# Laser_Array_Temp.net
KiCad netlist of a schematic drawn in EAGLE
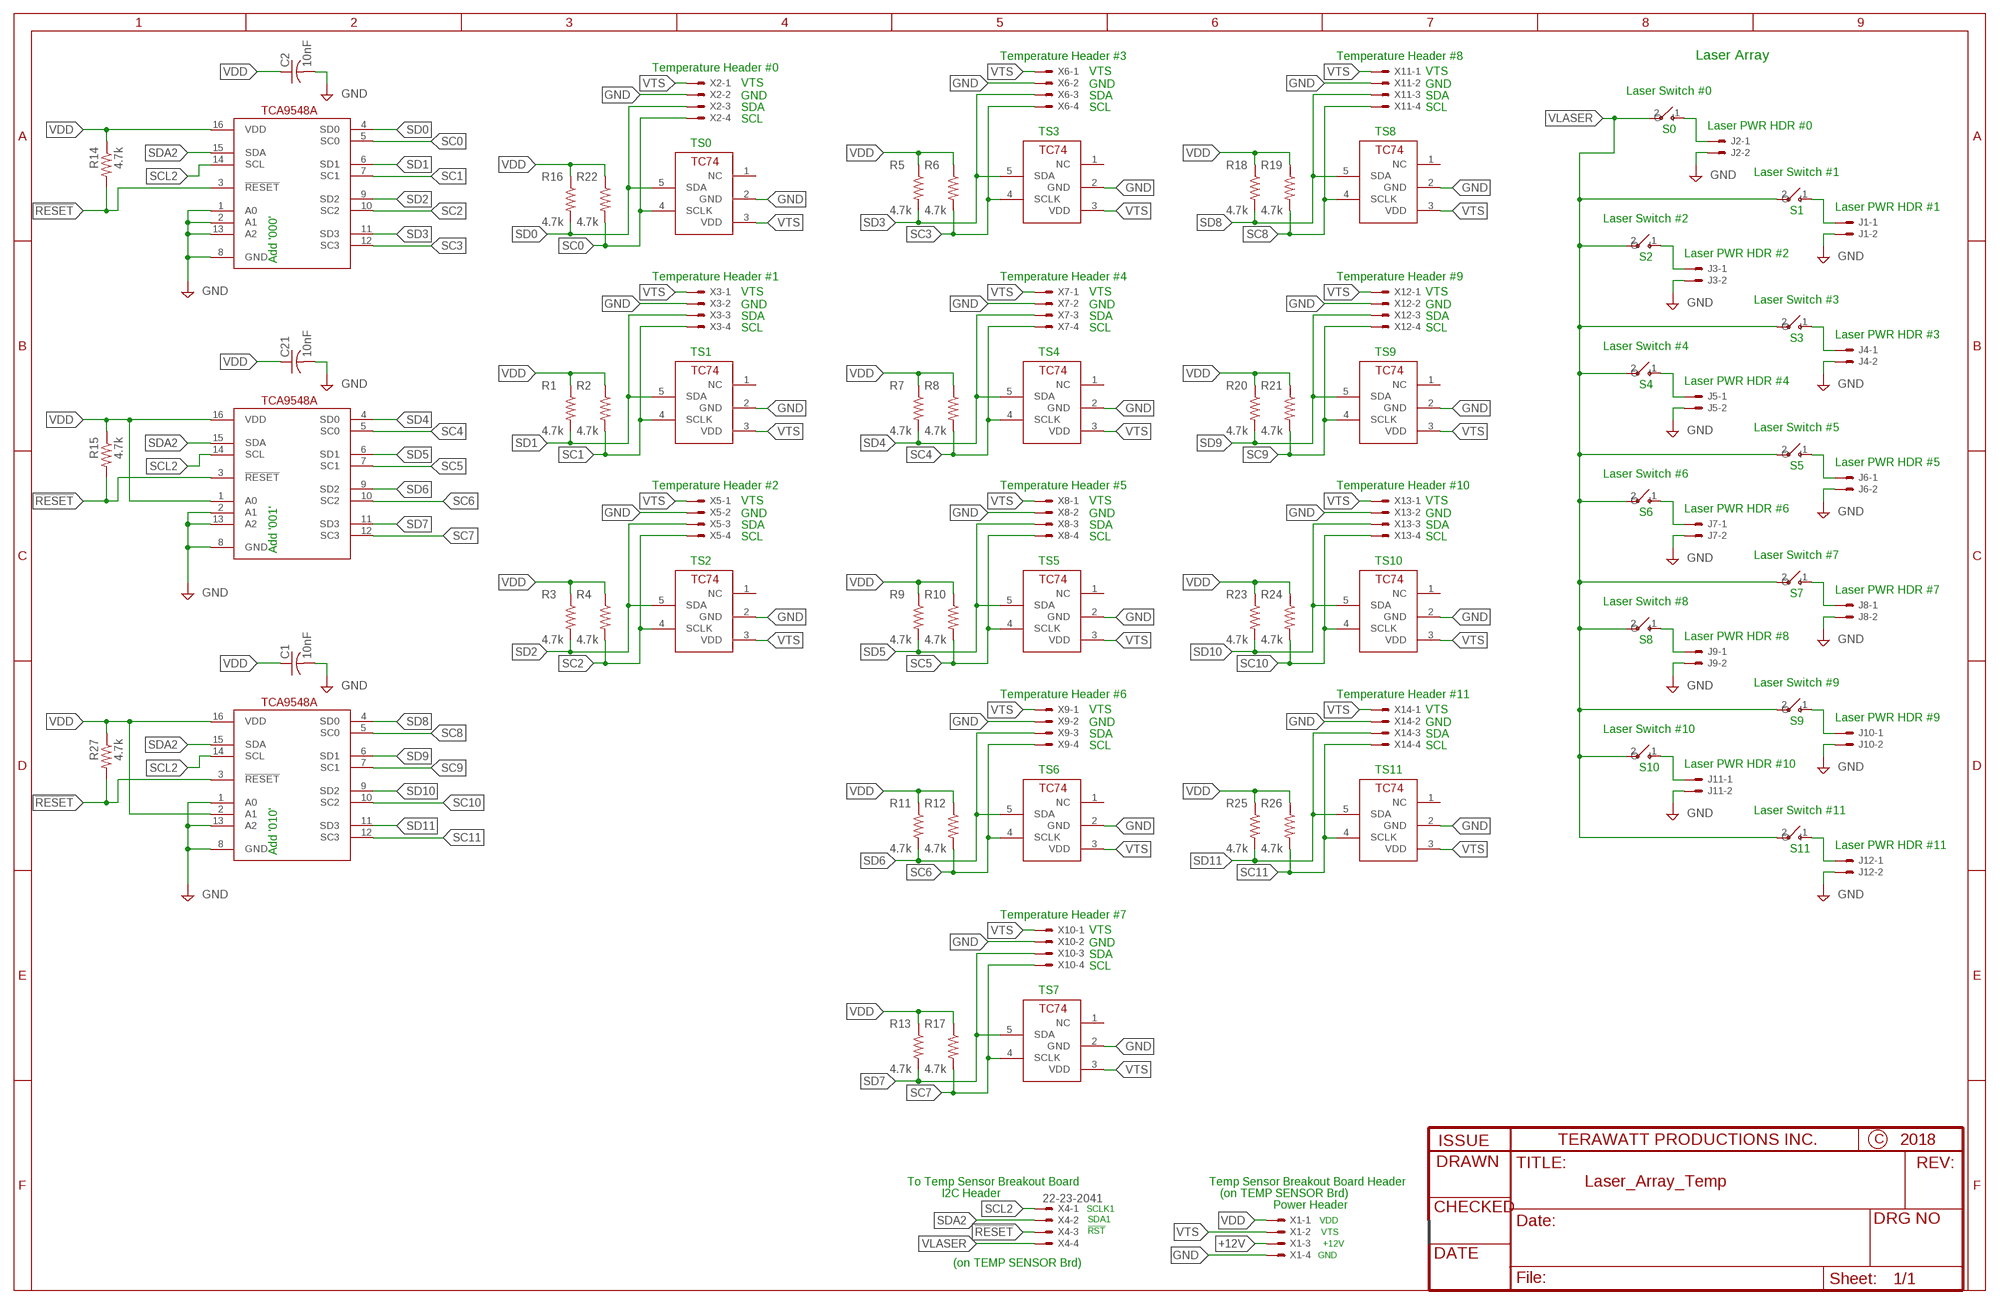
[diagram p0: schematic, sheet 1]

(export (version "E")
  (design (tool "Eeschema 10.0.6"))
  (components
    (comp (ref "C1")
      (value "10nF")
      (footprint "eagle-import:C0805")
      (libsource (lib "eagle-import") (part "C-USC0805"))
    )
    (comp (ref "C2")
      (value "10nF")
      (footprint "eagle-import:C0805")
      (libsource (lib "eagle-import") (part "C-USC0805"))
    )
    (comp (ref "C21")
      (value "10nF")
      (footprint "eagle-import:C0805")
      (libsource (lib "eagle-import") (part "C-USC0805"))
    )
    (comp (ref "J1")
      (value "22-23-2021")
      (footprint "eagle-import:22-23-2021")
      (fields (field (name "MF") "MOLEX"))
      (libsource (lib "eagle-import") (part "22-23-2021"))
    )
    (comp (ref "J2")
      (value "22-23-2021")
      (footprint "eagle-import:22-23-2021")
      (fields (field (name "MF") "MOLEX"))
      (libsource (lib "eagle-import") (part "22-23-2021"))
    )
    (comp (ref "J3")
      (value "22-23-2021")
      (footprint "eagle-import:22-23-2021")
      (fields (field (name "MF") "MOLEX"))
      (libsource (lib "eagle-import") (part "22-23-2021"))
    )
    (comp (ref "J4")
      (value "22-23-2021")
      (footprint "eagle-import:22-23-2021")
      (fields (field (name "MF") "MOLEX"))
      (libsource (lib "eagle-import") (part "22-23-2021"))
    )
    (comp (ref "J5")
      (value "22-23-2021")
      (footprint "eagle-import:22-23-2021")
      (fields (field (name "MF") "MOLEX"))
      (libsource (lib "eagle-import") (part "22-23-2021"))
    )
    (comp (ref "J6")
      (value "22-23-2021")
      (footprint "eagle-import:22-23-2021")
      (fields (field (name "MF") "MOLEX"))
      (libsource (lib "eagle-import") (part "22-23-2021"))
    )
    (comp (ref "J7")
      (value "22-23-2021")
      (footprint "eagle-import:22-23-2021")
      (fields (field (name "MF") "MOLEX"))
      (libsource (lib "eagle-import") (part "22-23-2021"))
    )
    (comp (ref "J8")
      (value "22-23-2021")
      (footprint "eagle-import:22-23-2021")
      (fields (field (name "MF") "MOLEX"))
      (libsource (lib "eagle-import") (part "22-23-2021"))
    )
    (comp (ref "J9")
      (value "22-23-2021")
      (footprint "eagle-import:22-23-2021")
      (fields (field (name "MF") "MOLEX"))
      (libsource (lib "eagle-import") (part "22-23-2021"))
    )
    (comp (ref "J10")
      (value "22-23-2021")
      (footprint "eagle-import:22-23-2021")
      (fields (field (name "MF") "MOLEX"))
      (libsource (lib "eagle-import") (part "22-23-2021"))
    )
    (comp (ref "J11")
      (value "22-23-2021")
      (footprint "eagle-import:22-23-2021")
      (fields (field (name "MF") "MOLEX"))
      (libsource (lib "eagle-import") (part "22-23-2021"))
    )
    (comp (ref "J12")
      (value "22-23-2021")
      (footprint "eagle-import:22-23-2021")
      (fields (field (name "MF") "MOLEX"))
      (libsource (lib "eagle-import") (part "22-23-2021"))
    )
    (comp (ref "R1")
      (value "4.7k")
      (footprint "eagle-import:M0805")
      (libsource (lib "eagle-import") (part "R-US_M0805"))
    )
    (comp (ref "R2")
      (value "4.7k")
      (footprint "eagle-import:M0805")
      (libsource (lib "eagle-import") (part "R-US_M0805"))
    )
    (comp (ref "R3")
      (value "4.7k")
      (footprint "eagle-import:M0805")
      (libsource (lib "eagle-import") (part "R-US_M0805"))
    )
    (comp (ref "R4")
      (value "4.7k")
      (footprint "eagle-import:M0805")
      (libsource (lib "eagle-import") (part "R-US_M0805"))
    )
    (comp (ref "R5")
      (value "4.7k")
      (footprint "eagle-import:M0805")
      (libsource (lib "eagle-import") (part "R-US_M0805"))
    )
    (comp (ref "R6")
      (value "4.7k")
      (footprint "eagle-import:M0805")
      (libsource (lib "eagle-import") (part "R-US_M0805"))
    )
    (comp (ref "R7")
      (value "4.7k")
      (footprint "eagle-import:M0805")
      (libsource (lib "eagle-import") (part "R-US_M0805"))
    )
    (comp (ref "R8")
      (value "4.7k")
      (footprint "eagle-import:M0805")
      (libsource (lib "eagle-import") (part "R-US_M0805"))
    )
    (comp (ref "R9")
      (value "4.7k")
      (footprint "eagle-import:M0805")
      (libsource (lib "eagle-import") (part "R-US_M0805"))
    )
    (comp (ref "R10")
      (value "4.7k")
      (footprint "eagle-import:M0805")
      (libsource (lib "eagle-import") (part "R-US_M0805"))
    )
    (comp (ref "R11")
      (value "4.7k")
      (footprint "eagle-import:M0805")
      (libsource (lib "eagle-import") (part "R-US_M0805"))
    )
    (comp (ref "R12")
      (value "4.7k")
      (footprint "eagle-import:M0805")
      (libsource (lib "eagle-import") (part "R-US_M0805"))
    )
    (comp (ref "R13")
      (value "4.7k")
      (footprint "eagle-import:M0805")
      (libsource (lib "eagle-import") (part "R-US_M0805"))
    )
    (comp (ref "R14")
      (value "4.7k")
      (footprint "eagle-import:M0805")
      (libsource (lib "eagle-import") (part "R-US_M0805"))
    )
    (comp (ref "R15")
      (value "4.7k")
      (footprint "eagle-import:M0805")
      (libsource (lib "eagle-import") (part "R-US_M0805"))
    )
    (comp (ref "R16")
      (value "4.7k")
      (footprint "eagle-import:M0805")
      (libsource (lib "eagle-import") (part "R-US_M0805"))
    )
    (comp (ref "R17")
      (value "4.7k")
      (footprint "eagle-import:M0805")
      (libsource (lib "eagle-import") (part "R-US_M0805"))
    )
    (comp (ref "R18")
      (value "4.7k")
      (footprint "eagle-import:M0805")
      (libsource (lib "eagle-import") (part "R-US_M0805"))
    )
    (comp (ref "R19")
      (value "4.7k")
      (footprint "eagle-import:M0805")
      (libsource (lib "eagle-import") (part "R-US_M0805"))
    )
    (comp (ref "R20")
      (value "4.7k")
      (footprint "eagle-import:M0805")
      (libsource (lib "eagle-import") (part "R-US_M0805"))
    )
    (comp (ref "R21")
      (value "4.7k")
      (footprint "eagle-import:M0805")
      (libsource (lib "eagle-import") (part "R-US_M0805"))
    )
    (comp (ref "R22")
      (value "4.7k")
      (footprint "eagle-import:M0805")
      (libsource (lib "eagle-import") (part "R-US_M0805"))
    )
    (comp (ref "R23")
      (value "4.7k")
      (footprint "eagle-import:M0805")
      (libsource (lib "eagle-import") (part "R-US_M0805"))
    )
    (comp (ref "R24")
      (value "4.7k")
      (footprint "eagle-import:M0805")
      (libsource (lib "eagle-import") (part "R-US_M0805"))
    )
    (comp (ref "R25")
      (value "4.7k")
      (footprint "eagle-import:M0805")
      (libsource (lib "eagle-import") (part "R-US_M0805"))
    )
    (comp (ref "R26")
      (value "4.7k")
      (footprint "eagle-import:M0805")
      (libsource (lib "eagle-import") (part "R-US_M0805"))
    )
    (comp (ref "R27")
      (value "4.7k")
      (footprint "eagle-import:M0805")
      (libsource (lib "eagle-import") (part "R-US_M0805"))
    )
    (comp (ref "S13")
      (value "TOGGLE_SPST")
      (footprint "eagle-import:22-23-2021")
      (libsource (lib "eagle-import") (part "TOGGLE_SPST"))
    )
    (comp (ref "S14")
      (value "TOGGLE_SPST")
      (footprint "eagle-import:22-23-2021")
      (libsource (lib "eagle-import") (part "TOGGLE_SPST"))
    )
    (comp (ref "S15")
      (value "TOGGLE_SPST")
      (footprint "eagle-import:22-23-2021")
      (libsource (lib "eagle-import") (part "TOGGLE_SPST"))
    )
    (comp (ref "S16")
      (value "TOGGLE_SPST")
      (footprint "eagle-import:22-23-2021")
      (libsource (lib "eagle-import") (part "TOGGLE_SPST"))
    )
    (comp (ref "S17")
      (value "TOGGLE_SPST")
      (footprint "eagle-import:22-23-2021")
      (libsource (lib "eagle-import") (part "TOGGLE_SPST"))
    )
    (comp (ref "S18")
      (value "TOGGLE_SPST")
      (footprint "eagle-import:22-23-2021")
      (libsource (lib "eagle-import") (part "TOGGLE_SPST"))
    )
    (comp (ref "S19")
      (value "TOGGLE_SPST")
      (footprint "eagle-import:22-23-2021")
      (libsource (lib "eagle-import") (part "TOGGLE_SPST"))
    )
    (comp (ref "S20")
      (value "TOGGLE_SPST")
      (footprint "eagle-import:22-23-2021")
      (libsource (lib "eagle-import") (part "TOGGLE_SPST"))
    )
    (comp (ref "S21")
      (value "TOGGLE_SPST")
      (footprint "eagle-import:22-23-2021")
      (libsource (lib "eagle-import") (part "TOGGLE_SPST"))
    )
    (comp (ref "S22")
      (value "TOGGLE_SPST")
      (footprint "eagle-import:22-23-2021")
      (libsource (lib "eagle-import") (part "TOGGLE_SPST"))
    )
    (comp (ref "S23")
      (value "TOGGLE_SPST")
      (footprint "eagle-import:22-23-2021")
      (libsource (lib "eagle-import") (part "TOGGLE_SPST"))
    )
    (comp (ref "S24")
      (value "TOGGLE_SPST")
      (footprint "eagle-import:22-23-2021")
      (libsource (lib "eagle-import") (part "TOGGLE_SPST"))
    )
    (comp (ref "TS1")
      (value "TC74")
      (footprint "eagle-import:SOT23-5L")
      (libsource (lib "eagle-import") (part "TC74"))
    )
    (comp (ref "TS2")
      (value "TC74")
      (footprint "eagle-import:SOT23-5L")
      (libsource (lib "eagle-import") (part "TC74"))
    )
    (comp (ref "TS3")
      (value "TC74")
      (footprint "eagle-import:SOT23-5L")
      (libsource (lib "eagle-import") (part "TC74"))
    )
    (comp (ref "TS4")
      (value "TC74")
      (footprint "eagle-import:SOT23-5L")
      (libsource (lib "eagle-import") (part "TC74"))
    )
    (comp (ref "TS5")
      (value "TC74")
      (footprint "eagle-import:SOT23-5L")
      (libsource (lib "eagle-import") (part "TC74"))
    )
    (comp (ref "TS6")
      (value "TC74")
      (footprint "eagle-import:SOT23-5L")
      (libsource (lib "eagle-import") (part "TC74"))
    )
    (comp (ref "TS7")
      (value "TC74")
      (footprint "eagle-import:SOT23-5L")
      (libsource (lib "eagle-import") (part "TC74"))
    )
    (comp (ref "TS8")
      (value "TC74")
      (footprint "eagle-import:SOT23-5L")
      (libsource (lib "eagle-import") (part "TC74"))
    )
    (comp (ref "TS9")
      (value "TC74")
      (footprint "eagle-import:SOT23-5L")
      (libsource (lib "eagle-import") (part "TC74"))
    )
    (comp (ref "TS10")
      (value "TC74")
      (footprint "eagle-import:SOT23-5L")
      (libsource (lib "eagle-import") (part "TC74"))
    )
    (comp (ref "TS11")
      (value "TC74")
      (footprint "eagle-import:SOT23-5L")
      (libsource (lib "eagle-import") (part "TC74"))
    )
    (comp (ref "TS12")
      (value "TC74")
      (footprint "eagle-import:SOT23-5L")
      (libsource (lib "eagle-import") (part "TC74"))
    )
    (comp (ref "U1")
      (value "TCA9546A")
      (footprint "eagle-import:SOIC16N")
      (libsource (lib "eagle-import") (part "TCA9546A"))
    )
    (comp (ref "U2")
      (value "TCA9546A")
      (footprint "eagle-import:SOIC16N")
      (libsource (lib "eagle-import") (part "TCA9546A"))
    )
    (comp (ref "U3")
      (value "TCA9546A")
      (footprint "eagle-import:SOIC16N")
      (libsource (lib "eagle-import") (part "TCA9546A"))
    )
    (comp (ref "X1")
      (value "22-23-2041")
      (footprint "eagle-import:22-23-2041")
      (fields (field (name "MF") "MOLEX"))
      (libsource (lib "eagle-import") (part "22-23-2041"))
    )
    (comp (ref "X2")
      (value "22-23-2041")
      (footprint "eagle-import:22-23-2041")
      (fields (field (name "MF") "MOLEX"))
      (libsource (lib "eagle-import") (part "22-23-2041"))
    )
    (comp (ref "X3")
      (value "22-23-2041")
      (footprint "eagle-import:22-23-2041")
      (fields (field (name "MF") "MOLEX"))
      (libsource (lib "eagle-import") (part "22-23-2041"))
    )
    (comp (ref "X4")
      (value "22-23-2041")
      (footprint "eagle-import:22-23-2041")
      (fields (field (name "MF") "MOLEX"))
      (libsource (lib "eagle-import") (part "22-23-2041"))
    )
    (comp (ref "X5")
      (value "22-23-2041")
      (footprint "eagle-import:22-23-2041")
      (fields (field (name "MF") "MOLEX"))
      (libsource (lib "eagle-import") (part "22-23-2041"))
    )
    (comp (ref "X6")
      (value "22-23-2041")
      (footprint "eagle-import:22-23-2041")
      (fields (field (name "MF") "MOLEX"))
      (libsource (lib "eagle-import") (part "22-23-2041"))
    )
    (comp (ref "X7")
      (value "22-23-2041")
      (footprint "eagle-import:22-23-2041")
      (fields (field (name "MF") "MOLEX"))
      (libsource (lib "eagle-import") (part "22-23-2041"))
    )
    (comp (ref "X8")
      (value "22-23-2041")
      (footprint "eagle-import:22-23-2041")
      (fields (field (name "MF") "MOLEX"))
      (libsource (lib "eagle-import") (part "22-23-2041"))
    )
    (comp (ref "X9")
      (value "22-23-2041")
      (footprint "eagle-import:22-23-2041")
      (fields (field (name "MF") "MOLEX"))
      (libsource (lib "eagle-import") (part "22-23-2041"))
    )
    (comp (ref "X10")
      (value "22-23-2041")
      (footprint "eagle-import:22-23-2041")
      (fields (field (name "MF") "MOLEX"))
      (libsource (lib "eagle-import") (part "22-23-2041"))
    )
    (comp (ref "X11")
      (value "22-23-2041")
      (footprint "eagle-import:22-23-2041")
      (fields (field (name "MF") "MOLEX"))
      (libsource (lib "eagle-import") (part "22-23-2041"))
    )
    (comp (ref "X12")
      (value "22-23-2041")
      (footprint "eagle-import:22-23-2041")
      (fields (field (name "MF") "MOLEX"))
      (libsource (lib "eagle-import") (part "22-23-2041"))
    )
    (comp (ref "X13")
      (value "22-23-2041")
      (footprint "eagle-import:22-23-2041")
      (fields (field (name "MF") "MOLEX"))
      (libsource (lib "eagle-import") (part "22-23-2041"))
    )
    (comp (ref "X14")
      (value "22-23-2041")
      (footprint "eagle-import:22-23-2041")
      (fields (field (name "MF") "MOLEX"))
      (libsource (lib "eagle-import") (part "22-23-2041"))
    )
  )
  (nets
    (net (code "1") (name "+12V") (class "Default")
      (node (ref "X1") (pin "3") (pinfunction "S_3") (pintype "passive"))
    )
    (net (code "2") (name "/~{RESET}") (class "Default")
      (node (ref "R14") (pin "2") (pinfunction "2_2") (pintype "passive"))
      (node (ref "R15") (pin "2") (pinfunction "2_2") (pintype "passive"))
      (node (ref "R27") (pin "2") (pinfunction "2_2") (pintype "passive"))
      (node (ref "U1") (pin "3") (pinfunction "~{RESET}_3") (pintype "bidirectional"))
      (node (ref "U2") (pin "3") (pinfunction "~{RESET}_3") (pintype "bidirectional"))
      (node (ref "U3") (pin "3") (pinfunction "~{RESET}_3") (pintype "bidirectional"))
      (node (ref "X4") (pin "3") (pinfunction "S_3") (pintype "passive"))
    )
    (net (code "3") (name "GND") (class "Default")
      (node (ref "C1") (pin "2") (pinfunction "2_2") (pintype "passive"))
      (node (ref "C2") (pin "2") (pinfunction "2_2") (pintype "passive"))
      (node (ref "C21") (pin "2") (pinfunction "2_2") (pintype "passive"))
      (node (ref "J1") (pin "2") (pinfunction "S_2") (pintype "passive"))
      (node (ref "J10") (pin "2") (pinfunction "S_2") (pintype "passive"))
      (node (ref "J11") (pin "2") (pinfunction "S_2") (pintype "passive"))
      (node (ref "J12") (pin "2") (pinfunction "S_2") (pintype "passive"))
      (node (ref "J2") (pin "2") (pinfunction "S_2") (pintype "passive"))
      (node (ref "J3") (pin "2") (pinfunction "S_2") (pintype "passive"))
      (node (ref "J4") (pin "2") (pinfunction "S_2") (pintype "passive"))
      (node (ref "J5") (pin "2") (pinfunction "S_2") (pintype "passive"))
      (node (ref "J6") (pin "2") (pinfunction "S_2") (pintype "passive"))
      (node (ref "J7") (pin "2") (pinfunction "S_2") (pintype "passive"))
      (node (ref "J8") (pin "2") (pinfunction "S_2") (pintype "passive"))
      (node (ref "J9") (pin "2") (pinfunction "S_2") (pintype "passive"))
      (node (ref "TS1") (pin "2") (pinfunction "GND_2") (pintype "bidirectional"))
      (node (ref "TS10") (pin "2") (pinfunction "GND_2") (pintype "bidirectional"))
      (node (ref "TS11") (pin "2") (pinfunction "GND_2") (pintype "bidirectional"))
      (node (ref "TS12") (pin "2") (pinfunction "GND_2") (pintype "bidirectional"))
      (node (ref "TS2") (pin "2") (pinfunction "GND_2") (pintype "bidirectional"))
      (node (ref "TS3") (pin "2") (pinfunction "GND_2") (pintype "bidirectional"))
      (node (ref "TS4") (pin "2") (pinfunction "GND_2") (pintype "bidirectional"))
      (node (ref "TS5") (pin "2") (pinfunction "GND_2") (pintype "bidirectional"))
      (node (ref "TS6") (pin "2") (pinfunction "GND_2") (pintype "bidirectional"))
      (node (ref "TS7") (pin "2") (pinfunction "GND_2") (pintype "bidirectional"))
      (node (ref "TS8") (pin "2") (pinfunction "GND_2") (pintype "bidirectional"))
      (node (ref "TS9") (pin "2") (pinfunction "GND_2") (pintype "bidirectional"))
      (node (ref "U1") (pin "1") (pinfunction "A0_1") (pintype "bidirectional"))
      (node (ref "U1") (pin "13") (pinfunction "A2_13") (pintype "bidirectional"))
      (node (ref "U1") (pin "2") (pinfunction "A1_2") (pintype "bidirectional"))
      (node (ref "U1") (pin "8") (pinfunction "GND_8") (pintype "bidirectional"))
      (node (ref "U2") (pin "13") (pinfunction "A2_13") (pintype "bidirectional"))
      (node (ref "U2") (pin "2") (pinfunction "A1_2") (pintype "bidirectional"))
      (node (ref "U2") (pin "8") (pinfunction "GND_8") (pintype "bidirectional"))
      (node (ref "U3") (pin "1") (pinfunction "A0_1") (pintype "bidirectional"))
      (node (ref "U3") (pin "13") (pinfunction "A2_13") (pintype "bidirectional"))
      (node (ref "U3") (pin "8") (pinfunction "GND_8") (pintype "bidirectional"))
      (node (ref "X1") (pin "4") (pinfunction "S_4") (pintype "passive"))
      (node (ref "X10") (pin "2") (pinfunction "S_2") (pintype "passive"))
      (node (ref "X11") (pin "2") (pinfunction "S_2") (pintype "passive"))
      (node (ref "X12") (pin "2") (pinfunction "S_2") (pintype "passive"))
      (node (ref "X13") (pin "2") (pinfunction "S_2") (pintype "passive"))
      (node (ref "X14") (pin "2") (pinfunction "S_2") (pintype "passive"))
      (node (ref "X2") (pin "2") (pinfunction "S_2") (pintype "passive"))
      (node (ref "X3") (pin "2") (pinfunction "S_2") (pintype "passive"))
      (node (ref "X5") (pin "2") (pinfunction "S_2") (pintype "passive"))
      (node (ref "X6") (pin "2") (pinfunction "S_2") (pintype "passive"))
      (node (ref "X7") (pin "2") (pinfunction "S_2") (pintype "passive"))
      (node (ref "X8") (pin "2") (pinfunction "S_2") (pintype "passive"))
      (node (ref "X9") (pin "2") (pinfunction "S_2") (pintype "passive"))
    )
    (net (code "4") (name "Net-(J1A-S)") (class "Default")
      (node (ref "J1") (pin "1") (pinfunction "S_1") (pintype "passive"))
      (node (ref "S13") (pin "1") (pinfunction "O_1") (pintype "bidirectional"))
    )
    (net (code "5") (name "Net-(J2A-S)") (class "Default")
      (node (ref "J2") (pin "1") (pinfunction "S_1") (pintype "passive"))
      (node (ref "S16") (pin "1") (pinfunction "O_1") (pintype "bidirectional"))
    )
    (net (code "6") (name "Net-(J3A-S)") (class "Default")
      (node (ref "J3") (pin "1") (pinfunction "S_1") (pintype "passive"))
      (node (ref "S14") (pin "1") (pinfunction "O_1") (pintype "bidirectional"))
    )
    (net (code "7") (name "Net-(J4A-S)") (class "Default")
      (node (ref "J4") (pin "1") (pinfunction "S_1") (pintype "passive"))
      (node (ref "S15") (pin "1") (pinfunction "O_1") (pintype "bidirectional"))
    )
    (net (code "8") (name "Net-(J5A-S)") (class "Default")
      (node (ref "J5") (pin "1") (pinfunction "S_1") (pintype "passive"))
      (node (ref "S17") (pin "1") (pinfunction "O_1") (pintype "bidirectional"))
    )
    (net (code "9") (name "Net-(J6A-S)") (class "Default")
      (node (ref "J6") (pin "1") (pinfunction "S_1") (pintype "passive"))
      (node (ref "S18") (pin "1") (pinfunction "O_1") (pintype "bidirectional"))
    )
    (net (code "10") (name "Net-(J7A-S)") (class "Default")
      (node (ref "J7") (pin "1") (pinfunction "S_1") (pintype "passive"))
      (node (ref "S19") (pin "1") (pinfunction "O_1") (pintype "bidirectional"))
    )
    (net (code "11") (name "Net-(J8A-S)") (class "Default")
      (node (ref "J8") (pin "1") (pinfunction "S_1") (pintype "passive"))
      (node (ref "S20") (pin "1") (pinfunction "O_1") (pintype "bidirectional"))
    )
    (net (code "12") (name "Net-(J9A-S)") (class "Default")
      (node (ref "J9") (pin "1") (pinfunction "S_1") (pintype "passive"))
      (node (ref "S21") (pin "1") (pinfunction "O_1") (pintype "bidirectional"))
    )
    (net (code "13") (name "Net-(J10A-S)") (class "Default")
      (node (ref "J10") (pin "1") (pinfunction "S_1") (pintype "passive"))
      (node (ref "S22") (pin "1") (pinfunction "O_1") (pintype "bidirectional"))
    )
    (net (code "14") (name "Net-(J11A-S)") (class "Default")
      (node (ref "J11") (pin "1") (pinfunction "S_1") (pintype "passive"))
      (node (ref "S23") (pin "1") (pinfunction "O_1") (pintype "bidirectional"))
    )
    (net (code "15") (name "Net-(J12A-S)") (class "Default")
      (node (ref "J12") (pin "1") (pinfunction "S_1") (pintype "passive"))
      (node (ref "S24") (pin "1") (pinfunction "O_1") (pintype "bidirectional"))
    )
    (net (code "16") (name "SC0") (class "Default")
      (node (ref "R22") (pin "2") (pinfunction "2_2") (pintype "passive"))
      (node (ref "TS1") (pin "4") (pinfunction "SCLK_4") (pintype "bidirectional"))
      (node (ref "U1") (pin "5") (pinfunction "SC0_5") (pintype "bidirectional"))
      (node (ref "X2") (pin "4") (pinfunction "S_4") (pintype "passive"))
    )
    (net (code "17") (name "SC1") (class "Default")
      (node (ref "R2") (pin "2") (pinfunction "2_2") (pintype "passive"))
      (node (ref "TS2") (pin "4") (pinfunction "SCLK_4") (pintype "bidirectional"))
      (node (ref "U1") (pin "7") (pinfunction "SC1_7") (pintype "bidirectional"))
      (node (ref "X3") (pin "4") (pinfunction "S_4") (pintype "passive"))
    )
    (net (code "18") (name "SC2") (class "Default")
      (node (ref "R4") (pin "2") (pinfunction "2_2") (pintype "passive"))
      (node (ref "TS3") (pin "4") (pinfunction "SCLK_4") (pintype "bidirectional"))
      (node (ref "U1") (pin "10") (pinfunction "SC2_10") (pintype "bidirectional"))
      (node (ref "X5") (pin "4") (pinfunction "S_4") (pintype "passive"))
    )
    (net (code "19") (name "SC3") (class "Default")
      (node (ref "R6") (pin "2") (pinfunction "2_2") (pintype "passive"))
      (node (ref "TS4") (pin "4") (pinfunction "SCLK_4") (pintype "bidirectional"))
      (node (ref "U1") (pin "12") (pinfunction "SC3_12") (pintype "bidirectional"))
      (node (ref "X6") (pin "4") (pinfunction "S_4") (pintype "passive"))
    )
    (net (code "20") (name "SC4") (class "Default")
      (node (ref "R8") (pin "2") (pinfunction "2_2") (pintype "passive"))
      (node (ref "TS5") (pin "4") (pinfunction "SCLK_4") (pintype "bidirectional"))
      (node (ref "U2") (pin "5") (pinfunction "SC0_5") (pintype "bidirectional"))
      (node (ref "X7") (pin "4") (pinfunction "S_4") (pintype "passive"))
    )
    (net (code "21") (name "SC5") (class "Default")
      (node (ref "R10") (pin "2") (pinfunction "2_2") (pintype "passive"))
      (node (ref "TS6") (pin "4") (pinfunction "SCLK_4") (pintype "bidirectional"))
      (node (ref "U2") (pin "7") (pinfunction "SC1_7") (pintype "bidirectional"))
      (node (ref "X8") (pin "4") (pinfunction "S_4") (pintype "passive"))
    )
    (net (code "22") (name "SC6") (class "Default")
      (node (ref "R12") (pin "2") (pinfunction "2_2") (pintype "passive"))
      (node (ref "TS7") (pin "4") (pinfunction "SCLK_4") (pintype "bidirectional"))
      (node (ref "U2") (pin "10") (pinfunction "SC2_10") (pintype "bidirectional"))
      (node (ref "X9") (pin "4") (pinfunction "S_4") (pintype "passive"))
    )
    (net (code "23") (name "SC7") (class "Default")
      (node (ref "R17") (pin "2") (pinfunction "2_2") (pintype "passive"))
      (node (ref "TS8") (pin "4") (pinfunction "SCLK_4") (pintype "bidirectional"))
      (node (ref "U2") (pin "12") (pinfunction "SC3_12") (pintype "bidirectional"))
      (node (ref "X10") (pin "4") (pinfunction "S_4") (pintype "passive"))
    )
    (net (code "24") (name "SC8") (class "Default")
      (node (ref "R19") (pin "2") (pinfunction "2_2") (pintype "passive"))
      (node (ref "TS9") (pin "4") (pinfunction "SCLK_4") (pintype "bidirectional"))
      (node (ref "U3") (pin "5") (pinfunction "SC0_5") (pintype "bidirectional"))
      (node (ref "X11") (pin "4") (pinfunction "S_4") (pintype "passive"))
    )
    (net (code "25") (name "SC9") (class "Default")
      (node (ref "R21") (pin "2") (pinfunction "2_2") (pintype "passive"))
      (node (ref "TS10") (pin "4") (pinfunction "SCLK_4") (pintype "bidirectional"))
      (node (ref "U3") (pin "7") (pinfunction "SC1_7") (pintype "bidirectional"))
      (node (ref "X12") (pin "4") (pinfunction "S_4") (pintype "passive"))
    )
    (net (code "26") (name "SC10") (class "Default")
      (node (ref "R24") (pin "2") (pinfunction "2_2") (pintype "passive"))
      (node (ref "TS11") (pin "4") (pinfunction "SCLK_4") (pintype "bidirectional"))
      (node (ref "U3") (pin "10") (pinfunction "SC2_10") (pintype "bidirectional"))
      (node (ref "X13") (pin "4") (pinfunction "S_4") (pintype "passive"))
    )
    (net (code "27") (name "SC11") (class "Default")
      (node (ref "R26") (pin "2") (pinfunction "2_2") (pintype "passive"))
      (node (ref "TS12") (pin "4") (pinfunction "SCLK_4") (pintype "bidirectional"))
      (node (ref "U3") (pin "12") (pinfunction "SC3_12") (pintype "bidirectional"))
      (node (ref "X14") (pin "4") (pinfunction "S_4") (pintype "passive"))
    )
    (net (code "28") (name "SCL2") (class "Default")
      (node (ref "U1") (pin "14") (pinfunction "SCL_14") (pintype "bidirectional"))
      (node (ref "U2") (pin "14") (pinfunction "SCL_14") (pintype "bidirectional"))
      (node (ref "U3") (pin "14") (pinfunction "SCL_14") (pintype "bidirectional"))
      (node (ref "X4") (pin "1") (pinfunction "S_1") (pintype "passive"))
    )
    (net (code "29") (name "SD0") (class "Default")
      (node (ref "R16") (pin "2") (pinfunction "2_2") (pintype "passive"))
      (node (ref "TS1") (pin "5") (pinfunction "SDA_5") (pintype "bidirectional"))
      (node (ref "U1") (pin "4") (pinfunction "SD0_4") (pintype "bidirectional"))
      (node (ref "X2") (pin "3") (pinfunction "S_3") (pintype "passive"))
    )
    (net (code "30") (name "SD1") (class "Default")
      (node (ref "R1") (pin "2") (pinfunction "2_2") (pintype "passive"))
      (node (ref "TS2") (pin "5") (pinfunction "SDA_5") (pintype "bidirectional"))
      (node (ref "U1") (pin "6") (pinfunction "SD1_6") (pintype "bidirectional"))
      (node (ref "X3") (pin "3") (pinfunction "S_3") (pintype "passive"))
    )
    (net (code "31") (name "SD2") (class "Default")
      (node (ref "R3") (pin "2") (pinfunction "2_2") (pintype "passive"))
      (node (ref "TS3") (pin "5") (pinfunction "SDA_5") (pintype "bidirectional"))
      (node (ref "U1") (pin "9") (pinfunction "SD2_9") (pintype "bidirectional"))
      (node (ref "X5") (pin "3") (pinfunction "S_3") (pintype "passive"))
    )
    (net (code "32") (name "SD3") (class "Default")
      (node (ref "R5") (pin "2") (pinfunction "2_2") (pintype "passive"))
      (node (ref "TS4") (pin "5") (pinfunction "SDA_5") (pintype "bidirectional"))
      (node (ref "U1") (pin "11") (pinfunction "SD3_11") (pintype "bidirectional"))
      (node (ref "X6") (pin "3") (pinfunction "S_3") (pintype "passive"))
    )
    (net (code "33") (name "SD4") (class "Default")
      (node (ref "R7") (pin "2") (pinfunction "2_2") (pintype "passive"))
      (node (ref "TS5") (pin "5") (pinfunction "SDA_5") (pintype "bidirectional"))
      (node (ref "U2") (pin "4") (pinfunction "SD0_4") (pintype "bidirectional"))
      (node (ref "X7") (pin "3") (pinfunction "S_3") (pintype "passive"))
    )
    (net (code "34") (name "SD5") (class "Default")
      (node (ref "R9") (pin "2") (pinfunction "2_2") (pintype "passive"))
      (node (ref "TS6") (pin "5") (pinfunction "SDA_5") (pintype "bidirectional"))
      (node (ref "U2") (pin "6") (pinfunction "SD1_6") (pintype "bidirectional"))
      (node (ref "X8") (pin "3") (pinfunction "S_3") (pintype "passive"))
    )
    (net (code "35") (name "SD6") (class "Default")
      (node (ref "R11") (pin "2") (pinfunction "2_2") (pintype "passive"))
      (node (ref "TS7") (pin "5") (pinfunction "SDA_5") (pintype "bidirectional"))
      (node (ref "U2") (pin "9") (pinfunction "SD2_9") (pintype "bidirectional"))
      (node (ref "X9") (pin "3") (pinfunction "S_3") (pintype "passive"))
    )
    (net (code "36") (name "SD7") (class "Default")
      (node (ref "R13") (pin "2") (pinfunction "2_2") (pintype "passive"))
      (node (ref "TS8") (pin "5") (pinfunction "SDA_5") (pintype "bidirectional"))
      (node (ref "U2") (pin "11") (pinfunction "SD3_11") (pintype "bidirectional"))
      (node (ref "X10") (pin "3") (pinfunction "S_3") (pintype "passive"))
    )
    (net (code "37") (name "SD8") (class "Default")
      (node (ref "R18") (pin "2") (pinfunction "2_2") (pintype "passive"))
      (node (ref "TS9") (pin "5") (pinfunction "SDA_5") (pintype "bidirectional"))
      (node (ref "U3") (pin "4") (pinfunction "SD0_4") (pintype "bidirectional"))
      (node (ref "X11") (pin "3") (pinfunction "S_3") (pintype "passive"))
    )
    (net (code "38") (name "SD9") (class "Default")
      (node (ref "R20") (pin "2") (pinfunction "2_2") (pintype "passive"))
      (node (ref "TS10") (pin "5") (pinfunction "SDA_5") (pintype "bidirectional"))
      (node (ref "U3") (pin "6") (pinfunction "SD1_6") (pintype "bidirectional"))
      (node (ref "X12") (pin "3") (pinfunction "S_3") (pintype "passive"))
    )
    (net (code "39") (name "SD10") (class "Default")
      (node (ref "R23") (pin "2") (pinfunction "2_2") (pintype "passive"))
      (node (ref "TS11") (pin "5") (pinfunction "SDA_5") (pintype "bidirectional"))
      (node (ref "U3") (pin "9") (pinfunction "SD2_9") (pintype "bidirectional"))
      (node (ref "X13") (pin "3") (pinfunction "S_3") (pintype "passive"))
    )
    (net (code "40") (name "SD11") (class "Default")
      (node (ref "R25") (pin "2") (pinfunction "2_2") (pintype "passive"))
      (node (ref "TS12") (pin "5") (pinfunction "SDA_5") (pintype "bidirectional"))
      (node (ref "U3") (pin "11") (pinfunction "SD3_11") (pintype "bidirectional"))
      (node (ref "X14") (pin "3") (pinfunction "S_3") (pintype "passive"))
    )
    (net (code "41") (name "SDA2") (class "Default")
      (node (ref "U1") (pin "15") (pinfunction "SDA_15") (pintype "bidirectional"))
      (node (ref "U2") (pin "15") (pinfunction "SDA_15") (pintype "bidirectional"))
      (node (ref "U3") (pin "15") (pinfunction "SDA_15") (pintype "bidirectional"))
      (node (ref "X4") (pin "2") (pinfunction "S_2") (pintype "passive"))
    )
    (net (code "42") (name "VDD") (class "Default")
      (node (ref "C1") (pin "1") (pinfunction "1_1") (pintype "passive"))
      (node (ref "C2") (pin "1") (pinfunction "1_1") (pintype "passive"))
      (node (ref "C21") (pin "1") (pinfunction "1_1") (pintype "passive"))
      (node (ref "R1") (pin "1") (pinfunction "1_1") (pintype "passive"))
      (node (ref "R10") (pin "1") (pinfunction "1_1") (pintype "passive"))
      (node (ref "R11") (pin "1") (pinfunction "1_1") (pintype "passive"))
      (node (ref "R12") (pin "1") (pinfunction "1_1") (pintype "passive"))
      (node (ref "R13") (pin "1") (pinfunction "1_1") (pintype "passive"))
      (node (ref "R14") (pin "1") (pinfunction "1_1") (pintype "passive"))
      (node (ref "R15") (pin "1") (pinfunction "1_1") (pintype "passive"))
      (node (ref "R16") (pin "1") (pinfunction "1_1") (pintype "passive"))
      (node (ref "R17") (pin "1") (pinfunction "1_1") (pintype "passive"))
      (node (ref "R18") (pin "1") (pinfunction "1_1") (pintype "passive"))
      (node (ref "R19") (pin "1") (pinfunction "1_1") (pintype "passive"))
      (node (ref "R2") (pin "1") (pinfunction "1_1") (pintype "passive"))
      (node (ref "R20") (pin "1") (pinfunction "1_1") (pintype "passive"))
      (node (ref "R21") (pin "1") (pinfunction "1_1") (pintype "passive"))
      (node (ref "R22") (pin "1") (pinfunction "1_1") (pintype "passive"))
      (node (ref "R23") (pin "1") (pinfunction "1_1") (pintype "passive"))
      (node (ref "R24") (pin "1") (pinfunction "1_1") (pintype "passive"))
      (node (ref "R25") (pin "1") (pinfunction "1_1") (pintype "passive"))
      (node (ref "R26") (pin "1") (pinfunction "1_1") (pintype "passive"))
      (node (ref "R27") (pin "1") (pinfunction "1_1") (pintype "passive"))
      (node (ref "R3") (pin "1") (pinfunction "1_1") (pintype "passive"))
      (node (ref "R4") (pin "1") (pinfunction "1_1") (pintype "passive"))
      (node (ref "R5") (pin "1") (pinfunction "1_1") (pintype "passive"))
      (node (ref "R6") (pin "1") (pinfunction "1_1") (pintype "passive"))
      (node (ref "R7") (pin "1") (pinfunction "1_1") (pintype "passive"))
      (node (ref "R8") (pin "1") (pinfunction "1_1") (pintype "passive"))
      (node (ref "R9") (pin "1") (pinfunction "1_1") (pintype "passive"))
      (node (ref "U1") (pin "16") (pinfunction "VDD_16") (pintype "bidirectional"))
      (node (ref "U2") (pin "1") (pinfunction "A0_1") (pintype "bidirectional"))
      (node (ref "U2") (pin "16") (pinfunction "VDD_16") (pintype "bidirectional"))
      (node (ref "U3") (pin "16") (pinfunction "VDD_16") (pintype "bidirectional"))
      (node (ref "U3") (pin "2") (pinfunction "A1_2") (pintype "bidirectional"))
      (node (ref "X1") (pin "1") (pinfunction "S_1") (pintype "passive"))
    )
    (net (code "43") (name "VLASER") (class "Default")
      (node (ref "S13") (pin "2") (pinfunction "I_2") (pintype "bidirectional"))
      (node (ref "S14") (pin "2") (pinfunction "I_2") (pintype "bidirectional"))
      (node (ref "S15") (pin "2") (pinfunction "I_2") (pintype "bidirectional"))
      (node (ref "S16") (pin "2") (pinfunction "I_2") (pintype "bidirectional"))
      (node (ref "S17") (pin "2") (pinfunction "I_2") (pintype "bidirectional"))
      (node (ref "S18") (pin "2") (pinfunction "I_2") (pintype "bidirectional"))
      (node (ref "S19") (pin "2") (pinfunction "I_2") (pintype "bidirectional"))
      (node (ref "S20") (pin "2") (pinfunction "I_2") (pintype "bidirectional"))
      (node (ref "S21") (pin "2") (pinfunction "I_2") (pintype "bidirectional"))
      (node (ref "S22") (pin "2") (pinfunction "I_2") (pintype "bidirectional"))
      (node (ref "S23") (pin "2") (pinfunction "I_2") (pintype "bidirectional"))
      (node (ref "S24") (pin "2") (pinfunction "I_2") (pintype "bidirectional"))
      (node (ref "X4") (pin "4") (pinfunction "S_4") (pintype "passive"))
    )
    (net (code "44") (name "VTS") (class "Default")
      (node (ref "TS1") (pin "3") (pinfunction "VDD_3") (pintype "bidirectional"))
      (node (ref "TS10") (pin "3") (pinfunction "VDD_3") (pintype "bidirectional"))
      (node (ref "TS11") (pin "3") (pinfunction "VDD_3") (pintype "bidirectional"))
      (node (ref "TS12") (pin "3") (pinfunction "VDD_3") (pintype "bidirectional"))
      (node (ref "TS2") (pin "3") (pinfunction "VDD_3") (pintype "bidirectional"))
      (node (ref "TS3") (pin "3") (pinfunction "VDD_3") (pintype "bidirectional"))
      (node (ref "TS4") (pin "3") (pinfunction "VDD_3") (pintype "bidirectional"))
      (node (ref "TS5") (pin "3") (pinfunction "VDD_3") (pintype "bidirectional"))
      (node (ref "TS6") (pin "3") (pinfunction "VDD_3") (pintype "bidirectional"))
      (node (ref "TS7") (pin "3") (pinfunction "VDD_3") (pintype "bidirectional"))
      (node (ref "TS8") (pin "3") (pinfunction "VDD_3") (pintype "bidirectional"))
      (node (ref "TS9") (pin "3") (pinfunction "VDD_3") (pintype "bidirectional"))
      (node (ref "X1") (pin "2") (pinfunction "S_2") (pintype "passive"))
      (node (ref "X10") (pin "1") (pinfunction "S_1") (pintype "passive"))
      (node (ref "X11") (pin "1") (pinfunction "S_1") (pintype "passive"))
      (node (ref "X12") (pin "1") (pinfunction "S_1") (pintype "passive"))
      (node (ref "X13") (pin "1") (pinfunction "S_1") (pintype "passive"))
      (node (ref "X14") (pin "1") (pinfunction "S_1") (pintype "passive"))
      (node (ref "X2") (pin "1") (pinfunction "S_1") (pintype "passive"))
      (node (ref "X3") (pin "1") (pinfunction "S_1") (pintype "passive"))
      (node (ref "X5") (pin "1") (pinfunction "S_1") (pintype "passive"))
      (node (ref "X6") (pin "1") (pinfunction "S_1") (pintype "passive"))
      (node (ref "X7") (pin "1") (pinfunction "S_1") (pintype "passive"))
      (node (ref "X8") (pin "1") (pinfunction "S_1") (pintype "passive"))
      (node (ref "X9") (pin "1") (pinfunction "S_1") (pintype "passive"))
    )
    (net (code "45") (name "unconnected-(TS1-NC-Pad1)") (class "Default")
      (node (ref "TS1") (pin "1") (pinfunction "NC_1") (pintype "bidirectional"))
    )
    (net (code "46") (name "unconnected-(TS2-NC-Pad1)") (class "Default")
      (node (ref "TS2") (pin "1") (pinfunction "NC_1") (pintype "bidirectional"))
    )
    (net (code "47") (name "unconnected-(TS3-NC-Pad1)") (class "Default")
      (node (ref "TS3") (pin "1") (pinfunction "NC_1") (pintype "bidirectional"))
    )
    (net (code "48") (name "unconnected-(TS4-NC-Pad1)") (class "Default")
      (node (ref "TS4") (pin "1") (pinfunction "NC_1") (pintype "bidirectional"))
    )
    (net (code "49") (name "unconnected-(TS5-NC-Pad1)") (class "Default")
      (node (ref "TS5") (pin "1") (pinfunction "NC_1") (pintype "bidirectional"))
    )
    (net (code "50") (name "unconnected-(TS6-NC-Pad1)") (class "Default")
      (node (ref "TS6") (pin "1") (pinfunction "NC_1") (pintype "bidirectional"))
    )
    (net (code "51") (name "unconnected-(TS7-NC-Pad1)") (class "Default")
      (node (ref "TS7") (pin "1") (pinfunction "NC_1") (pintype "bidirectional"))
    )
    (net (code "52") (name "unconnected-(TS8-NC-Pad1)") (class "Default")
      (node (ref "TS8") (pin "1") (pinfunction "NC_1") (pintype "bidirectional"))
    )
    (net (code "53") (name "unconnected-(TS9-NC-Pad1)") (class "Default")
      (node (ref "TS9") (pin "1") (pinfunction "NC_1") (pintype "bidirectional"))
    )
    (net (code "54") (name "unconnected-(TS10-NC-Pad1)") (class "Default")
      (node (ref "TS10") (pin "1") (pinfunction "NC_1") (pintype "bidirectional"))
    )
    (net (code "55") (name "unconnected-(TS11-NC-Pad1)") (class "Default")
      (node (ref "TS11") (pin "1") (pinfunction "NC_1") (pintype "bidirectional"))
    )
    (net (code "56") (name "unconnected-(TS12-NC-Pad1)") (class "Default")
      (node (ref "TS12") (pin "1") (pinfunction "NC_1") (pintype "bidirectional"))
    )
  )
)
